# RF22BController_v01.net
KiCad netlist of a schematic drawn in EAGLE
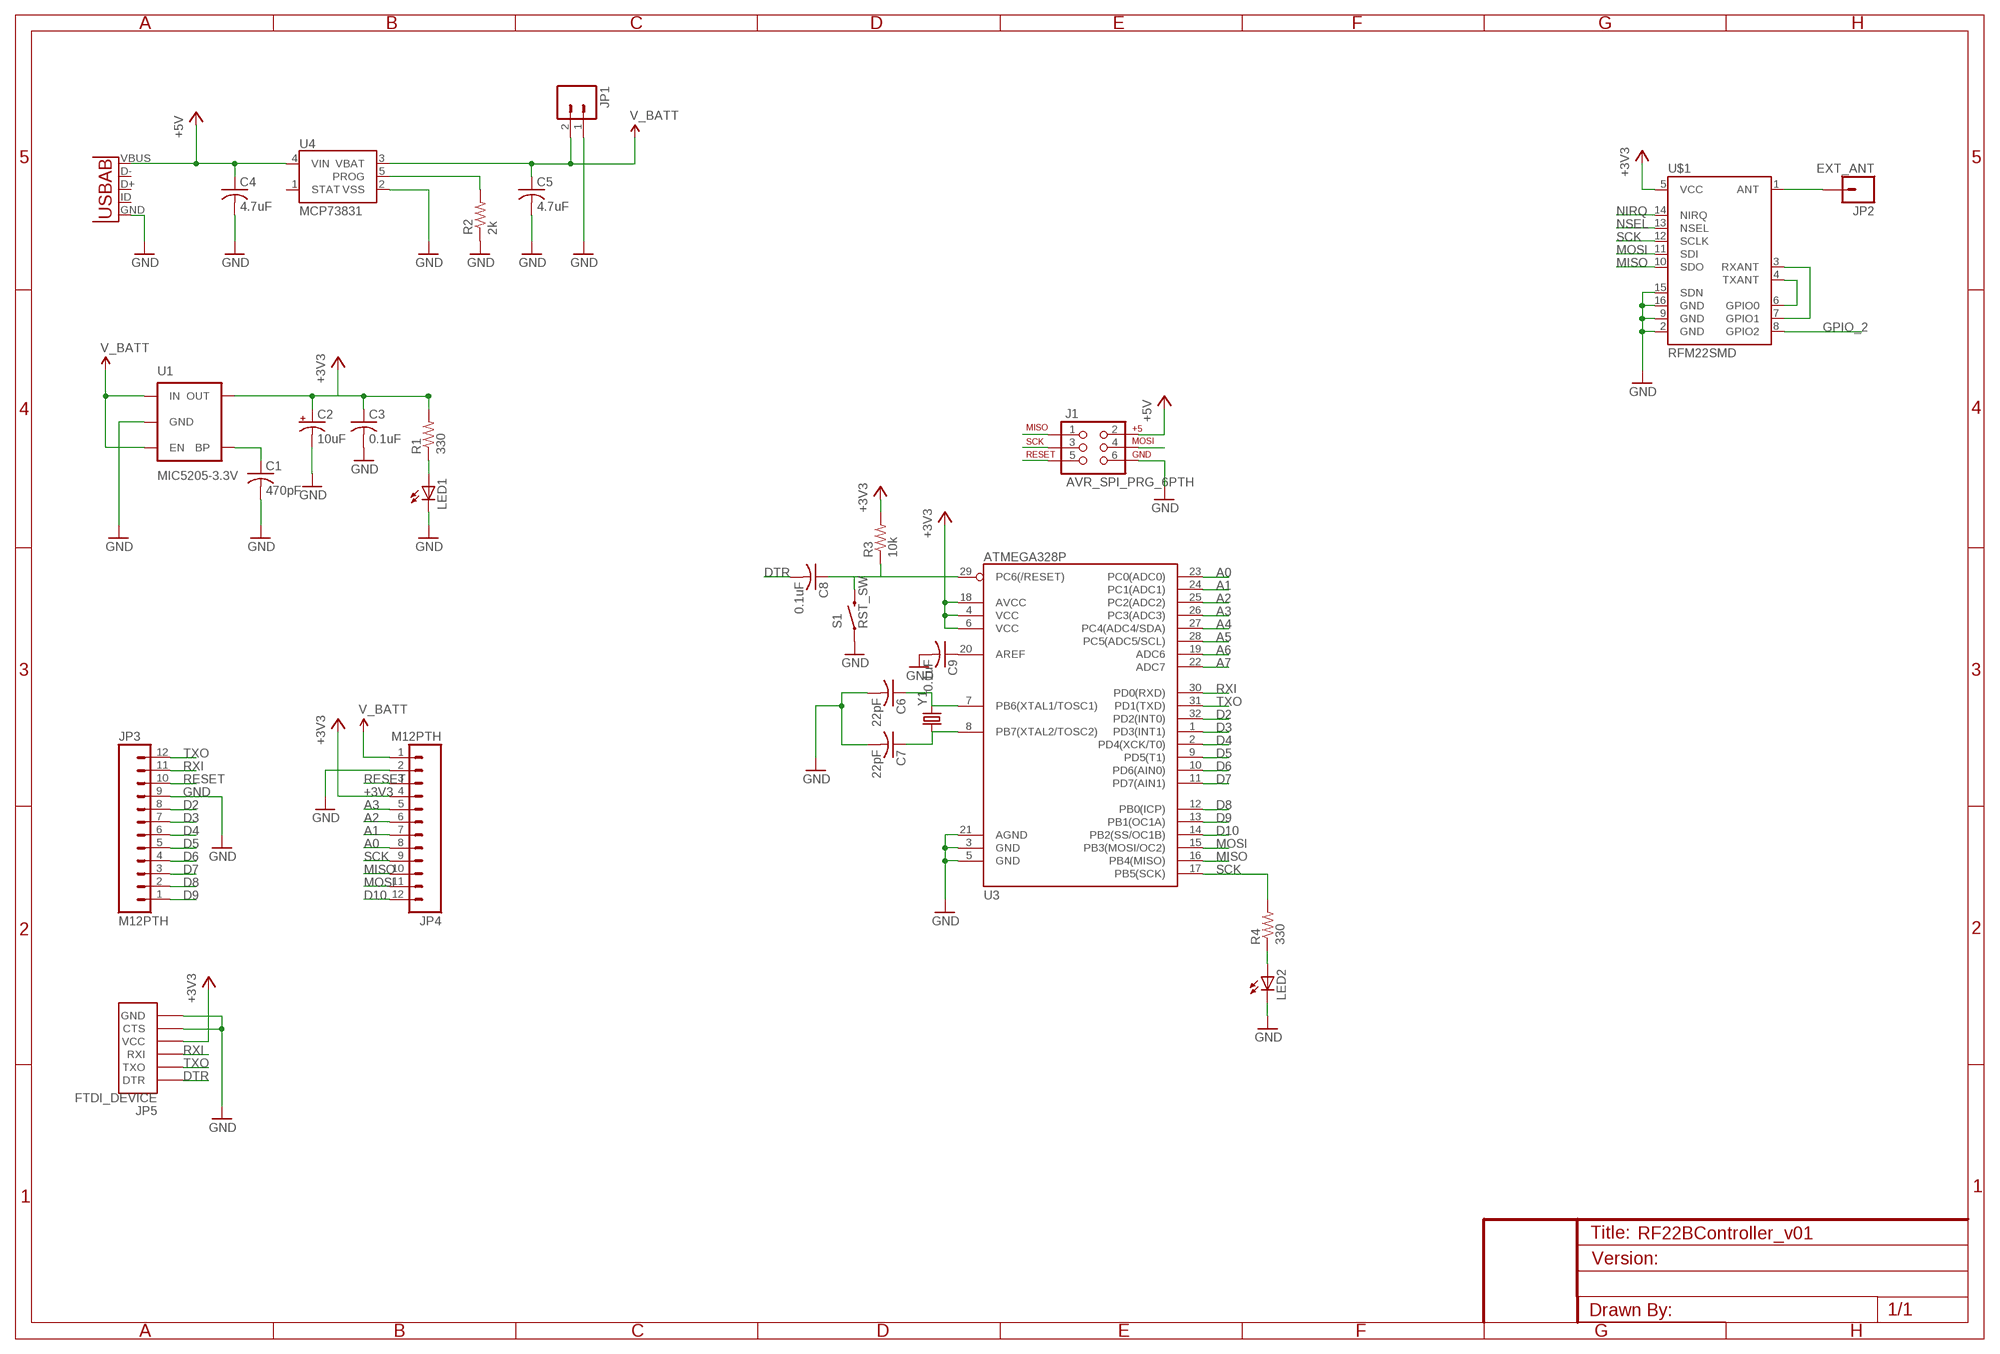
[diagram p0: schematic, sheet 1]

(export (version "E")
  (design (tool "Eeschema 10.0.6"))
  (components
    (comp (ref "C1")
      (value "470pF")
      (footprint "eagle-import:C0805")
      (libsource (lib "eagle-import") (part "C-USC0805"))
    )
    (comp (ref "C2")
      (value "10uF")
      (footprint "eagle-import:CT6032")
      (libsource (lib "eagle-import") (part "CPOL-USCT6032"))
    )
    (comp (ref "C3")
      (value "0.1uF")
      (footprint "eagle-import:C0805")
      (libsource (lib "eagle-import") (part "C-USC0805"))
    )
    (comp (ref "C4")
      (value "4.7uF")
      (footprint "eagle-import:C0805")
      (libsource (lib "eagle-import") (part "C-USC0805"))
    )
    (comp (ref "C5")
      (value "4.7uF")
      (footprint "eagle-import:C0805")
      (libsource (lib "eagle-import") (part "C-USC0805"))
    )
    (comp (ref "C6")
      (value "22pF")
      (footprint "eagle-import:C0805")
      (libsource (lib "eagle-import") (part "C-USC0805"))
    )
    (comp (ref "C7")
      (value "22pF")
      (footprint "eagle-import:C0805")
      (libsource (lib "eagle-import") (part "C-USC0805"))
    )
    (comp (ref "C8")
      (value "0.1uF")
      (footprint "eagle-import:C0805")
      (libsource (lib "eagle-import") (part "C-USC0805"))
    )
    (comp (ref "C9")
      (value "0.1uF")
      (footprint "eagle-import:C0805")
      (libsource (lib "eagle-import") (part "C-USC0805"))
    )
    (comp (ref "J1")
      (value "AVR_SPI_PRG_6PTH")
      (footprint "eagle-import:2X3")
      (libsource (lib "eagle-import") (part "AVR_SPI_PRG_6PTH"))
    )
    (comp (ref "JP1")
      (value "M02-JST-2MM-SMT")
      (footprint "eagle-import:JST-2-SMD")
      (libsource (lib "eagle-import") (part "M02-JST-2MM-SMT"))
    )
    (comp (ref "JP2")
      (value "EXT_ANT")
      (footprint "eagle-import:1X01")
      (libsource (lib "eagle-import") (part "M01PTH"))
    )
    (comp (ref "JP3")
      (value "M12PTH")
      (footprint "eagle-import:1X12")
      (libsource (lib "eagle-import") (part "M12PTH"))
    )
    (comp (ref "JP4")
      (value "M12PTH")
      (footprint "eagle-import:1X12")
      (libsource (lib "eagle-import") (part "M12PTH"))
    )
    (comp (ref "JP5")
      (value "FTDI_DEVICE")
      (footprint "eagle-import:FTDI_DEVICE_SIDE")
      (libsource (lib "eagle-import") (part "FTDI_DEVICE"))
    )
    (comp (ref "LED1")
      (value "LEDCHIP-LED0603")
      (footprint "eagle-import:CHIP-LED0603")
      (libsource (lib "eagle-import") (part "LEDCHIP-LED0603"))
    )
    (comp (ref "LED2")
      (value "LEDCHIP-LED0603")
      (footprint "eagle-import:CHIP-LED0603")
      (libsource (lib "eagle-import") (part "LEDCHIP-LED0603"))
    )
    (comp (ref "R1")
      (value "330")
      (footprint "eagle-import:M0805")
      (libsource (lib "eagle-import") (part "R-US_M0805"))
    )
    (comp (ref "R2")
      (value "2k")
      (footprint "eagle-import:M0805")
      (libsource (lib "eagle-import") (part "R-US_M0805"))
    )
    (comp (ref "R3")
      (value "10k")
      (footprint "eagle-import:M0805")
      (libsource (lib "eagle-import") (part "R-US_M0805"))
    )
    (comp (ref "R4")
      (value "330")
      (footprint "eagle-import:M0805")
      (libsource (lib "eagle-import") (part "R-US_M0805"))
    )
    (comp (ref "S1")
      (value "RST_SW")
      (footprint "eagle-import:TACTILE_SWITCH_TALL")
      (libsource (lib "eagle-import") (part "SWITCH-MOMENTARY-2"))
    )
    (comp (ref "U$1")
      (value "RFM22SMD")
      (footprint "eagle-import:RFM22-XXX-S2")
      (libsource (lib "eagle-import") (part "RFM22SMD"))
    )
    (comp (ref "U1")
      (value "MIC5205-3.3V")
      (footprint "eagle-import:SOT23-5")
      (libsource (lib "eagle-import") (part "MIC52053.3V"))
    )
    (comp (ref "U2")
      (value "USB-AB")
      (footprint "eagle-import:USB-AB-MICRO-SMD")
      (libsource (lib "eagle-import") (part "USB-AB"))
    )
    (comp (ref "U3")
      (value "ATMEGA328P")
      (footprint "eagle-import:TQFP32-08")
      (libsource (lib "eagle-import") (part "ATMEGA328_SMT"))
    )
    (comp (ref "U4")
      (value "MCP73831")
      (footprint "eagle-import:SOT23-5")
      (libsource (lib "eagle-import") (part "MCP73831"))
    )
    (comp (ref "Y1")
      (value "CRYSTALTXC-7A")
      (footprint "eagle-import:CRYSTAL-TXC-7A")
      (libsource (lib "eagle-import") (part "CRYSTALTXC-7A"))
    )
  )
  (nets
    (net (code "1") (name "+3V3") (class "Default")
      (node (ref "C2") (pin "+") (pinfunction "+_+") (pintype "passive"))
      (node (ref "C3") (pin "1") (pinfunction "1_1") (pintype "passive"))
      (node (ref "JP4") (pin "4") (pinfunction "4_4") (pintype "passive"))
      (node (ref "JP5") (pin "P$4") (pinfunction "VCC_P$4") (pintype "bidirectional"))
      (node (ref "R1") (pin "2") (pinfunction "2_2") (pintype "passive"))
      (node (ref "R3") (pin "2") (pinfunction "2_2") (pintype "passive"))
      (node (ref "U$1") (pin "5") (pinfunction "VCC_5") (pintype "bidirectional"))
      (node (ref "U1") (pin "5") (pinfunction "OUT_5") (pintype "passive"))
      (node (ref "U3") (pin "18") (pinfunction "AVCC_18") (pintype "bidirectional"))
      (node (ref "U3") (pin "4") (pinfunction "VCC_4") (pintype "bidirectional"))
      (node (ref "U3") (pin "6") (pinfunction "VCC_6") (pintype "bidirectional"))
    )
    (net (code "2") (name "+5V") (class "Default")
      (node (ref "C4") (pin "1") (pinfunction "1_1") (pintype "passive"))
      (node (ref "J1") (pin "2") (pinfunction "2_2") (pintype "passive"))
      (node (ref "U2") (pin "VBUS") (pinfunction "VBUS_VBUS") (pintype "bidirectional"))
      (node (ref "U4") (pin "4") (pinfunction "VIN_4") (pintype "power_in"))
    )
    (net (code "3") (name "/A0") (class "Default")
      (node (ref "JP4") (pin "8") (pinfunction "8_8") (pintype "passive"))
      (node (ref "U3") (pin "23") (pinfunction "PC0(ADC0)_23") (pintype "bidirectional"))
    )
    (net (code "4") (name "/A1") (class "Default")
      (node (ref "JP4") (pin "7") (pinfunction "7_7") (pintype "passive"))
      (node (ref "U3") (pin "24") (pinfunction "PC1(ADC1)_24") (pintype "bidirectional"))
    )
    (net (code "5") (name "/A2") (class "Default")
      (node (ref "JP4") (pin "6") (pinfunction "6_6") (pintype "passive"))
      (node (ref "U3") (pin "25") (pinfunction "PC2(ADC2)_25") (pintype "bidirectional"))
    )
    (net (code "6") (name "/A3") (class "Default")
      (node (ref "JP4") (pin "5") (pinfunction "5_5") (pintype "passive"))
      (node (ref "U3") (pin "26") (pinfunction "PC3(ADC3)_26") (pintype "bidirectional"))
    )
    (net (code "7") (name "/A4") (class "Default")
      (node (ref "U3") (pin "27") (pinfunction "PC4(ADC4/SDA)_27") (pintype "bidirectional"))
    )
    (net (code "8") (name "/A5") (class "Default")
      (node (ref "U3") (pin "28") (pinfunction "PC5(ADC5/SCL)_28") (pintype "bidirectional"))
    )
    (net (code "9") (name "/A6") (class "Default")
      (node (ref "U3") (pin "19") (pinfunction "ADC6_19") (pintype "bidirectional"))
    )
    (net (code "10") (name "/A7") (class "Default")
      (node (ref "U3") (pin "22") (pinfunction "ADC7_22") (pintype "bidirectional"))
    )
    (net (code "11") (name "/D2") (class "Default")
      (node (ref "JP3") (pin "8") (pinfunction "8_8") (pintype "passive"))
      (node (ref "U3") (pin "32") (pinfunction "PD2(INT0)_32") (pintype "bidirectional"))
    )
    (net (code "12") (name "/D3") (class "Default")
      (node (ref "JP3") (pin "7") (pinfunction "7_7") (pintype "passive"))
      (node (ref "U3") (pin "1") (pinfunction "PD3(INT1)_1") (pintype "bidirectional"))
    )
    (net (code "13") (name "/D4") (class "Default")
      (node (ref "JP3") (pin "6") (pinfunction "6_6") (pintype "passive"))
      (node (ref "U3") (pin "2") (pinfunction "PD4(XCK/T0)_2") (pintype "bidirectional"))
    )
    (net (code "14") (name "/D5") (class "Default")
      (node (ref "JP3") (pin "5") (pinfunction "5_5") (pintype "passive"))
      (node (ref "U3") (pin "9") (pinfunction "PD5(T1)_9") (pintype "bidirectional"))
    )
    (net (code "15") (name "/D6") (class "Default")
      (node (ref "JP3") (pin "4") (pinfunction "4_4") (pintype "passive"))
      (node (ref "U3") (pin "10") (pinfunction "PD6(AIN0)_10") (pintype "bidirectional"))
    )
    (net (code "16") (name "/D7") (class "Default")
      (node (ref "JP3") (pin "3") (pinfunction "3_3") (pintype "passive"))
      (node (ref "U3") (pin "11") (pinfunction "PD7(AIN1)_11") (pintype "bidirectional"))
    )
    (net (code "17") (name "/D8") (class "Default")
      (node (ref "JP3") (pin "2") (pinfunction "2_2") (pintype "passive"))
      (node (ref "U3") (pin "12") (pinfunction "PB0(ICP)_12") (pintype "bidirectional"))
    )
    (net (code "18") (name "/D9") (class "Default")
      (node (ref "JP3") (pin "1") (pinfunction "1_1") (pintype "passive"))
      (node (ref "U3") (pin "13") (pinfunction "PB1(OC1A)_13") (pintype "bidirectional"))
    )
    (net (code "19") (name "/D10") (class "Default")
      (node (ref "JP4") (pin "12") (pinfunction "12_12") (pintype "passive"))
      (node (ref "U3") (pin "14") (pinfunction "PB2(SS/OC1B)_14") (pintype "bidirectional"))
    )
    (net (code "20") (name "/DTR") (class "Default")
      (node (ref "C8") (pin "2") (pinfunction "2_2") (pintype "passive"))
      (node (ref "JP5") (pin "P$1") (pinfunction "DTR_P$1") (pintype "bidirectional"))
    )
    (net (code "21") (name "/GPIO_2") (class "Default")
      (node (ref "U$1") (pin "8") (pinfunction "GPIO2_8") (pintype "bidirectional"))
    )
    (net (code "22") (name "/MISO") (class "Default")
      (node (ref "J1") (pin "1") (pinfunction "1_1") (pintype "passive"))
      (node (ref "JP4") (pin "10") (pinfunction "10_10") (pintype "passive"))
      (node (ref "U$1") (pin "10") (pinfunction "SDO_10") (pintype "output"))
      (node (ref "U3") (pin "16") (pinfunction "PB4(MISO)_16") (pintype "bidirectional"))
    )
    (net (code "23") (name "/MOSI") (class "Default")
      (node (ref "J1") (pin "4") (pinfunction "4_4") (pintype "passive"))
      (node (ref "JP4") (pin "11") (pinfunction "11_11") (pintype "passive"))
      (node (ref "U$1") (pin "11") (pinfunction "SDI_11") (pintype "input"))
      (node (ref "U3") (pin "15") (pinfunction "PB3(MOSI/OC2)_15") (pintype "bidirectional"))
    )
    (net (code "24") (name "/NIRQ") (class "Default")
      (node (ref "U$1") (pin "14") (pinfunction "NIRQ_14") (pintype "output"))
    )
    (net (code "25") (name "/NSEL") (class "Default")
      (node (ref "U$1") (pin "13") (pinfunction "NSEL_13") (pintype "input"))
    )
    (net (code "26") (name "/RESET") (class "Default")
      (node (ref "C8") (pin "1") (pinfunction "1_1") (pintype "passive"))
      (node (ref "J1") (pin "5") (pinfunction "5_5") (pintype "passive"))
      (node (ref "JP3") (pin "10") (pinfunction "10_10") (pintype "passive"))
      (node (ref "JP4") (pin "3") (pinfunction "3_3") (pintype "passive"))
      (node (ref "R3") (pin "1") (pinfunction "1_1") (pintype "passive"))
      (node (ref "S1") (pin "B2") (pinfunction "2_B2") (pintype "passive"))
      (node (ref "U3") (pin "29") (pinfunction "PC6(/RESET)_29") (pintype "bidirectional"))
    )
    (net (code "27") (name "/RXI") (class "Default")
      (node (ref "JP3") (pin "11") (pinfunction "11_11") (pintype "passive"))
      (node (ref "JP5") (pin "P$3") (pinfunction "RXI_P$3") (pintype "bidirectional"))
      (node (ref "U3") (pin "30") (pinfunction "PD0(RXD)_30") (pintype "bidirectional"))
    )
    (net (code "28") (name "/SCK") (class "Default")
      (node (ref "J1") (pin "3") (pinfunction "3_3") (pintype "passive"))
      (node (ref "JP4") (pin "9") (pinfunction "9_9") (pintype "passive"))
      (node (ref "R4") (pin "2") (pinfunction "2_2") (pintype "passive"))
      (node (ref "U$1") (pin "12") (pinfunction "SCLK_12") (pintype "input"))
      (node (ref "U3") (pin "17") (pinfunction "PB5(SCK)_17") (pintype "bidirectional"))
    )
    (net (code "29") (name "/TXO") (class "Default")
      (node (ref "JP3") (pin "12") (pinfunction "12_12") (pintype "passive"))
      (node (ref "JP5") (pin "P$2") (pinfunction "TXO_P$2") (pintype "bidirectional"))
      (node (ref "U3") (pin "31") (pinfunction "PD1(TXD)_31") (pintype "bidirectional"))
    )
    (net (code "30") (name "GND") (class "Default")
      (node (ref "C1") (pin "2") (pinfunction "2_2") (pintype "passive"))
      (node (ref "C2") (pin "-") (pinfunction "-_-") (pintype "passive"))
      (node (ref "C3") (pin "2") (pinfunction "2_2") (pintype "passive"))
      (node (ref "C4") (pin "2") (pinfunction "2_2") (pintype "passive"))
      (node (ref "C5") (pin "2") (pinfunction "2_2") (pintype "passive"))
      (node (ref "C6") (pin "2") (pinfunction "2_2") (pintype "passive"))
      (node (ref "C7") (pin "2") (pinfunction "2_2") (pintype "passive"))
      (node (ref "C9") (pin "2") (pinfunction "2_2") (pintype "passive"))
      (node (ref "J1") (pin "6") (pinfunction "6_6") (pintype "passive"))
      (node (ref "JP1") (pin "1") (pinfunction "2_1") (pintype "passive"))
      (node (ref "JP3") (pin "9") (pinfunction "9_9") (pintype "passive"))
      (node (ref "JP4") (pin "2") (pinfunction "2_2") (pintype "passive"))
      (node (ref "JP5") (pin "P$5") (pinfunction "CTS_P$5") (pintype "bidirectional"))
      (node (ref "JP5") (pin "P$6") (pinfunction "GND_P$6") (pintype "bidirectional"))
      (node (ref "LED1") (pin "C") (pinfunction "C_C") (pintype "passive"))
      (node (ref "LED2") (pin "C") (pinfunction "C_C") (pintype "passive"))
      (node (ref "R2") (pin "1") (pinfunction "1_1") (pintype "passive"))
      (node (ref "S1") (pin "A2") (pinfunction "1_A2") (pintype "passive"))
      (node (ref "U$1") (pin "15") (pinfunction "SDN_15") (pintype "input"))
      (node (ref "U$1") (pin "16") (pinfunction "GND_16") (pintype "power_in"))
      (node (ref "U$1") (pin "2") (pinfunction "GND_2") (pintype "power_in"))
      (node (ref "U$1") (pin "9") (pinfunction "GND_9") (pintype "power_in"))
      (node (ref "U1") (pin "2") (pinfunction "GND_2") (pintype "input"))
      (node (ref "U2") (pin "GND") (pinfunction "GND_GND") (pintype "bidirectional"))
      (node (ref "U3") (pin "21") (pinfunction "AGND_21") (pintype "bidirectional"))
      (node (ref "U3") (pin "3") (pinfunction "GND_3") (pintype "bidirectional"))
      (node (ref "U3") (pin "5") (pinfunction "GND_5") (pintype "bidirectional"))
      (node (ref "U4") (pin "2") (pinfunction "VSS_2") (pintype "power_in"))
    )
    (net (code "31") (name "Net-(LED1-PadA)") (class "Default")
      (node (ref "LED1") (pin "A") (pinfunction "A_A") (pintype "passive"))
      (node (ref "R1") (pin "1") (pinfunction "1_1") (pintype "passive"))
    )
    (net (code "32") (name "Net-(LED2-PadA)") (class "Default")
      (node (ref "LED2") (pin "A") (pinfunction "A_A") (pintype "passive"))
      (node (ref "R4") (pin "1") (pinfunction "1_1") (pintype "passive"))
    )
    (net (code "33") (name "Net-(U$1-ANT)") (class "Default")
      (node (ref "JP2") (pin "1") (pinfunction "1_1") (pintype "passive"))
      (node (ref "U$1") (pin "1") (pinfunction "ANT_1") (pintype "bidirectional"))
    )
    (net (code "34") (name "Net-(U$1-GPIO0)") (class "Default")
      (node (ref "U$1") (pin "4") (pinfunction "TXANT_4") (pintype "input"))
      (node (ref "U$1") (pin "6") (pinfunction "GPIO0_6") (pintype "bidirectional"))
    )
    (net (code "35") (name "Net-(U$1-GPIO1)") (class "Default")
      (node (ref "U$1") (pin "3") (pinfunction "RXANT_3") (pintype "input"))
      (node (ref "U$1") (pin "7") (pinfunction "GPIO1_7") (pintype "bidirectional"))
    )
    (net (code "36") (name "Net-(U1-BP)") (class "Default")
      (node (ref "C1") (pin "1") (pinfunction "1_1") (pintype "passive"))
      (node (ref "U1") (pin "4") (pinfunction "BP_4") (pintype "input"))
    )
    (net (code "37") (name "Net-(U3-AREF)") (class "Default")
      (node (ref "C9") (pin "1") (pinfunction "1_1") (pintype "passive"))
      (node (ref "U3") (pin "20") (pinfunction "AREF_20") (pintype "bidirectional"))
    )
    (net (code "38") (name "Net-(U3-PB6(XTAL1{slash}TOSC1))") (class "Default")
      (node (ref "C6") (pin "1") (pinfunction "1_1") (pintype "passive"))
      (node (ref "U3") (pin "7") (pinfunction "PB6(XTAL1/TOSC1)_7") (pintype "bidirectional"))
      (node (ref "Y1") (pin "P$2") (pinfunction "2_P$2") (pintype "passive"))
    )
    (net (code "39") (name "Net-(U3-PB7(XTAL2{slash}TOSC2))") (class "Default")
      (node (ref "C7") (pin "1") (pinfunction "1_1") (pintype "passive"))
      (node (ref "U3") (pin "8") (pinfunction "PB7(XTAL2/TOSC2)_8") (pintype "bidirectional"))
      (node (ref "Y1") (pin "P$1") (pinfunction "1_P$1") (pintype "passive"))
    )
    (net (code "40") (name "Net-(U4-PROG)") (class "Default")
      (node (ref "R2") (pin "2") (pinfunction "2_2") (pintype "passive"))
      (node (ref "U4") (pin "5") (pinfunction "PROG_5") (pintype "input"))
    )
    (net (code "41") (name "V_BATT") (class "Default")
      (node (ref "C5") (pin "1") (pinfunction "1_1") (pintype "passive"))
      (node (ref "JP1") (pin "2") (pinfunction "1_2") (pintype "passive"))
      (node (ref "JP4") (pin "1") (pinfunction "1_1") (pintype "passive"))
      (node (ref "U1") (pin "1") (pinfunction "IN_1") (pintype "input"))
      (node (ref "U1") (pin "3") (pinfunction "EN_3") (pintype "input"))
      (node (ref "U4") (pin "3") (pinfunction "VBAT_3") (pintype "power_in"))
    )
    (net (code "42") (name "unconnected-(U2-PadD+)") (class "Default")
      (node (ref "U2") (pin "D+") (pinfunction "D+_D+") (pintype "bidirectional"))
    )
    (net (code "43") (name "unconnected-(U2-PadD-)") (class "Default")
      (node (ref "U2") (pin "D-") (pinfunction "D-_D-") (pintype "bidirectional"))
    )
    (net (code "44") (name "unconnected-(U2-USBID-PadID)") (class "Default")
      (node (ref "U2") (pin "ID") (pinfunction "USBID_ID") (pintype "bidirectional"))
    )
    (net (code "45") (name "unconnected-(U4-STAT-Pad1)") (class "Default")
      (node (ref "U4") (pin "1") (pinfunction "STAT_1") (pintype "output"))
    )
  )
)
